# Alimentation.net
KiCad netlist of a schematic drawn in Altium Designer
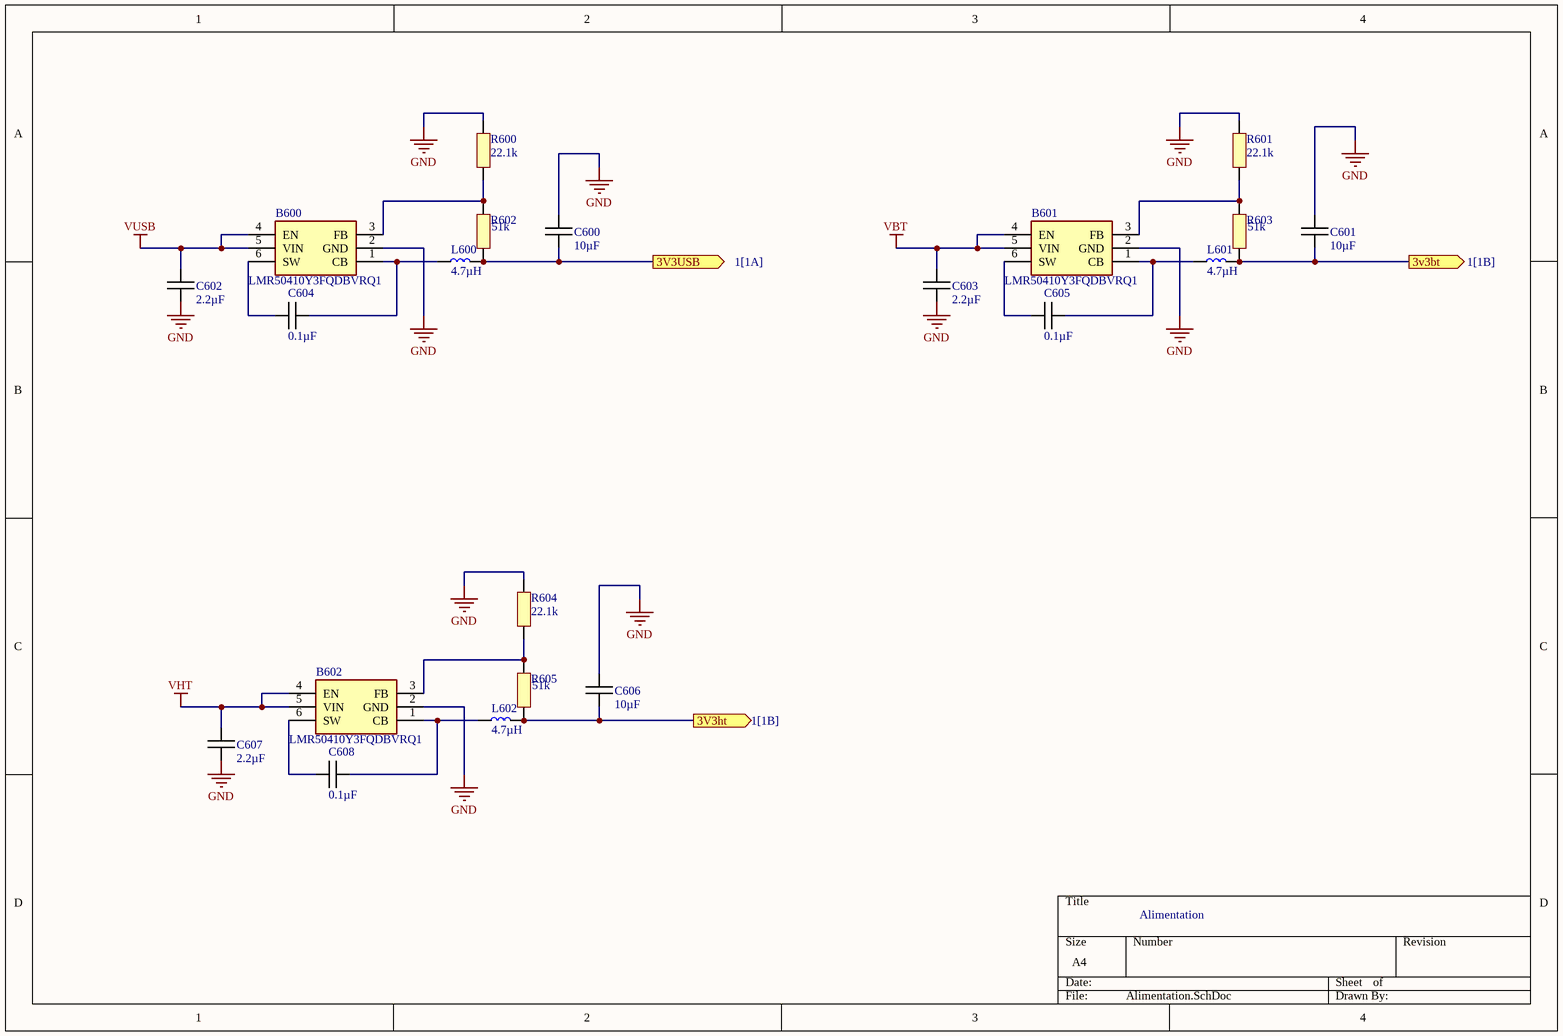
[diagram p0: Alimentation.SchDoc]

(export (version "E")
  (design (tool "Eeschema 10.0.6"))
  (components
    (comp (ref "B600")
      (value "LMR50410Y3FQDBVRQ1")
      (footprint "SOT95P280X145-6N")
      (fields (field (name "MOUSER PART NUMBER") "595-R50410Y3FQDBVRQ1"))
      (libsource (lib "SCHLibrary") (part "LMR50410Y3FQDBVRQ1"))
    )
    (comp (ref "B601")
      (value "LMR50410Y3FQDBVRQ1")
      (footprint "SOT95P280X145-6N")
      (fields (field (name "MOUSER PART NUMBER") "595-R50410Y3FQDBVRQ1"))
      (libsource (lib "SCHLibrary") (part "LMR50410Y3FQDBVRQ1"))
    )
    (comp (ref "B602")
      (value "LMR50410Y3FQDBVRQ1")
      (footprint "SOT95P280X145-6N")
      (fields (field (name "MOUSER PART NUMBER") "595-R50410Y3FQDBVRQ1"))
      (libsource (lib "SCHLibrary") (part "LMR50410Y3FQDBVRQ1"))
    )
    (comp (ref "C600")
      (value "10µF")
      (footprint "CAPC1005X06N")
      (libsource (lib "SCHLibrary") (part "Capacitor"))
    )
    (comp (ref "C601")
      (value "10µF")
      (footprint "CAPC1005X06N")
      (libsource (lib "SCHLibrary") (part "Capacitor"))
    )
    (comp (ref "C602")
      (value "2.2µF")
      (footprint "CAPC1005X06N")
      (libsource (lib "SCHLibrary") (part "Capacitor"))
    )
    (comp (ref "C603")
      (value "2.2µF")
      (footprint "CAPC1005X06N")
      (libsource (lib "SCHLibrary") (part "Capacitor"))
    )
    (comp (ref "C604")
      (value "0.1µF")
      (footprint "CAPC1005X06N")
      (libsource (lib "SCHLibrary") (part "Capacitor"))
    )
    (comp (ref "C605")
      (value "0.1µF")
      (footprint "CAPC1005X06N")
      (libsource (lib "SCHLibrary") (part "Capacitor"))
    )
    (comp (ref "C606")
      (value "10µF")
      (footprint "CAPC1005X06N")
      (libsource (lib "SCHLibrary") (part "Capacitor"))
    )
    (comp (ref "C607")
      (value "2.2µF")
      (footprint "CAPC1005X06N")
      (libsource (lib "SCHLibrary") (part "Capacitor"))
    )
    (comp (ref "C608")
      (value "0.1µF")
      (footprint "CAPC1005X06N")
      (libsource (lib "SCHLibrary") (part "Capacitor"))
    )
    (comp (ref "L600")
      (value "4.7µH")
      (footprint "LQPC1005X06N")
      (libsource (lib "SCHLibrary") (part "Bobine"))
    )
    (comp (ref "L601")
      (value "4.7µH")
      (footprint "LQPC1005X06N")
      (libsource (lib "SCHLibrary") (part "Bobine"))
    )
    (comp (ref "L602")
      (value "4.7µH")
      (footprint "LQPC1005X06N")
      (libsource (lib "SCHLibrary") (part "Bobine"))
    )
    (comp (ref "R600")
      (value "22.1k")
      (footprint "RESC1005X06N")
      (libsource (lib "SCHLibrary") (part "Resistor"))
    )
    (comp (ref "R601")
      (value "22.1k")
      (footprint "RESC1005X06N")
      (libsource (lib "SCHLibrary") (part "Resistor"))
    )
    (comp (ref "R602")
      (value "51k")
      (footprint "RESC1005X06N")
      (libsource (lib "SCHLibrary") (part "Resistor"))
    )
    (comp (ref "R603")
      (value "51k")
      (footprint "RESC1005X06N")
      (libsource (lib "SCHLibrary") (part "Resistor"))
    )
    (comp (ref "R604")
      (value "22.1k")
      (footprint "RESC1005X06N")
      (libsource (lib "SCHLibrary") (part "Resistor"))
    )
    (comp (ref "R605")
      (value "51k")
      (footprint "RESC1005X06N")
      (libsource (lib "SCHLibrary") (part "Resistor"))
    )
  )
  (nets
    (net (code "1") (name "/3V3USB") (class "Default")
      (node (ref "C600") (pin "2") (pinfunction "2_2") (pintype "passive"))
      (node (ref "L600") (pin "2") (pinfunction "2_2") (pintype "passive"))
      (node (ref "R602") (pin "1") (pinfunction "1_1") (pintype "passive"))
    )
    (net (code "2") (name "/3V3ht") (class "Default")
      (node (ref "C606") (pin "2") (pinfunction "2_2") (pintype "passive"))
      (node (ref "L602") (pin "2") (pinfunction "2_2") (pintype "passive"))
      (node (ref "R605") (pin "1") (pinfunction "1_1") (pintype "passive"))
    )
    (net (code "3") (name "/3v3bt") (class "Default")
      (node (ref "C601") (pin "2") (pinfunction "2_2") (pintype "passive"))
      (node (ref "L601") (pin "2") (pinfunction "2_2") (pintype "passive"))
      (node (ref "R603") (pin "1") (pinfunction "1_1") (pintype "passive"))
    )
    (net (code "4") (name "GND") (class "Default")
      (node (ref "B600") (pin "2") (pinfunction "GND_2") (pintype "passive"))
      (node (ref "B601") (pin "2") (pinfunction "GND_2") (pintype "passive"))
      (node (ref "B602") (pin "2") (pinfunction "GND_2") (pintype "passive"))
      (node (ref "C600") (pin "1") (pinfunction "1_1") (pintype "passive"))
      (node (ref "C601") (pin "1") (pinfunction "1_1") (pintype "passive"))
      (node (ref "C602") (pin "2") (pinfunction "2_2") (pintype "passive"))
      (node (ref "C603") (pin "2") (pinfunction "2_2") (pintype "passive"))
      (node (ref "C606") (pin "1") (pinfunction "1_1") (pintype "passive"))
      (node (ref "C607") (pin "2") (pinfunction "2_2") (pintype "passive"))
      (node (ref "R600") (pin "2") (pinfunction "2_2") (pintype "passive"))
      (node (ref "R601") (pin "2") (pinfunction "2_2") (pintype "passive"))
      (node (ref "R604") (pin "2") (pinfunction "2_2") (pintype "passive"))
    )
    (net (code "5") (name "Net-(B600-CB)") (class "Default")
      (node (ref "B600") (pin "1") (pinfunction "CB_1") (pintype "passive"))
      (node (ref "C604") (pin "1") (pinfunction "1_1") (pintype "passive"))
      (node (ref "L600") (pin "1") (pinfunction "1_1") (pintype "passive"))
    )
    (net (code "6") (name "Net-(B600-FB)") (class "Default")
      (node (ref "B600") (pin "3") (pinfunction "FB_3") (pintype "passive"))
      (node (ref "R600") (pin "1") (pinfunction "1_1") (pintype "passive"))
      (node (ref "R602") (pin "2") (pinfunction "2_2") (pintype "passive"))
    )
    (net (code "7") (name "Net-(B600-SW)") (class "Default")
      (node (ref "B600") (pin "6") (pinfunction "SW_6") (pintype "passive"))
      (node (ref "C604") (pin "2") (pinfunction "2_2") (pintype "passive"))
    )
    (net (code "8") (name "Net-(B601-CB)") (class "Default")
      (node (ref "B601") (pin "1") (pinfunction "CB_1") (pintype "passive"))
      (node (ref "C605") (pin "1") (pinfunction "1_1") (pintype "passive"))
      (node (ref "L601") (pin "1") (pinfunction "1_1") (pintype "passive"))
    )
    (net (code "9") (name "Net-(B601-FB)") (class "Default")
      (node (ref "B601") (pin "3") (pinfunction "FB_3") (pintype "passive"))
      (node (ref "R601") (pin "1") (pinfunction "1_1") (pintype "passive"))
      (node (ref "R603") (pin "2") (pinfunction "2_2") (pintype "passive"))
    )
    (net (code "10") (name "Net-(B601-SW)") (class "Default")
      (node (ref "B601") (pin "6") (pinfunction "SW_6") (pintype "passive"))
      (node (ref "C605") (pin "2") (pinfunction "2_2") (pintype "passive"))
    )
    (net (code "11") (name "Net-(B602-CB)") (class "Default")
      (node (ref "B602") (pin "1") (pinfunction "CB_1") (pintype "passive"))
      (node (ref "C608") (pin "1") (pinfunction "1_1") (pintype "passive"))
      (node (ref "L602") (pin "1") (pinfunction "1_1") (pintype "passive"))
    )
    (net (code "12") (name "Net-(B602-FB)") (class "Default")
      (node (ref "B602") (pin "3") (pinfunction "FB_3") (pintype "passive"))
      (node (ref "R604") (pin "1") (pinfunction "1_1") (pintype "passive"))
      (node (ref "R605") (pin "2") (pinfunction "2_2") (pintype "passive"))
    )
    (net (code "13") (name "Net-(B602-SW)") (class "Default")
      (node (ref "B602") (pin "6") (pinfunction "SW_6") (pintype "passive"))
      (node (ref "C608") (pin "2") (pinfunction "2_2") (pintype "passive"))
    )
    (net (code "14") (name "VBT") (class "Default")
      (node (ref "B601") (pin "4") (pinfunction "EN_4") (pintype "passive"))
      (node (ref "B601") (pin "5") (pinfunction "VIN_5") (pintype "passive"))
      (node (ref "C603") (pin "1") (pinfunction "1_1") (pintype "passive"))
    )
    (net (code "15") (name "VHT") (class "Default")
      (node (ref "B602") (pin "4") (pinfunction "EN_4") (pintype "passive"))
      (node (ref "B602") (pin "5") (pinfunction "VIN_5") (pintype "passive"))
      (node (ref "C607") (pin "1") (pinfunction "1_1") (pintype "passive"))
    )
    (net (code "16") (name "VUSB") (class "Default")
      (node (ref "B600") (pin "4") (pinfunction "EN_4") (pintype "passive"))
      (node (ref "B600") (pin "5") (pinfunction "VIN_5") (pintype "passive"))
      (node (ref "C602") (pin "1") (pinfunction "1_1") (pintype "passive"))
    )
  )
)
